# PCIe.net
KiCad netlist of a schematic drawn in Altium Designer
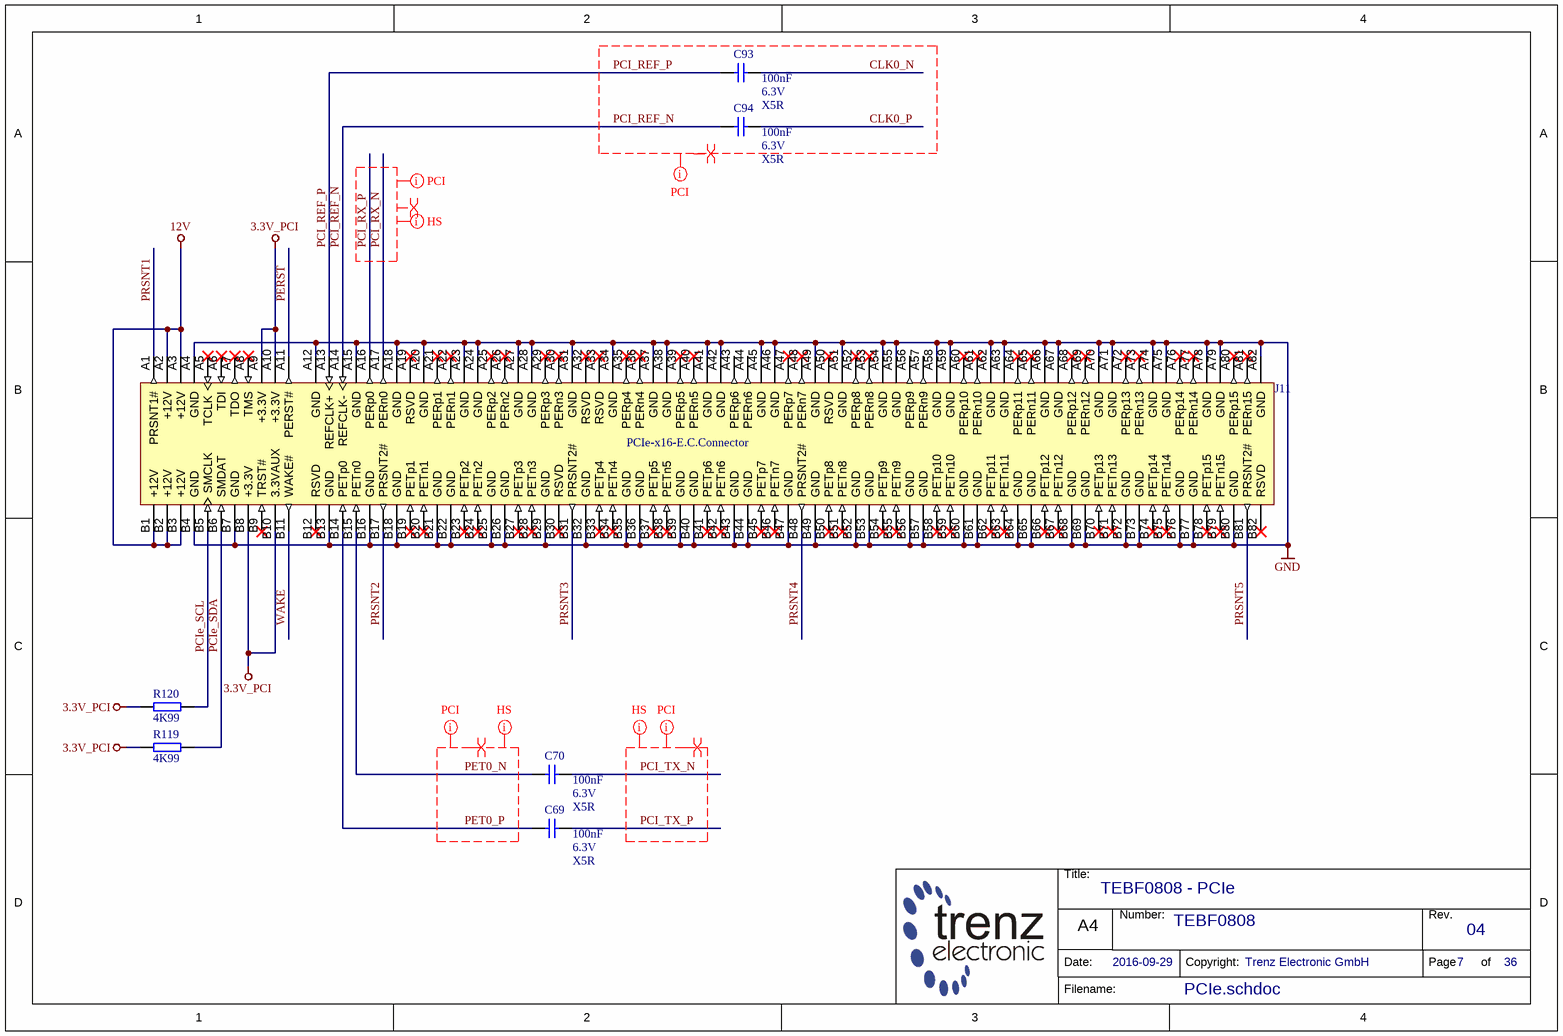
[diagram p0: PCIe.schdoc]

(export (version "E")
  (design (tool "Eeschema 10.0.6"))
  (components
    (comp (ref "C69")
      (value "100nF")
      (footprint "CAPC0603X33N")
      (description "KON 100nF 6.3V X5R SMD 10%")
      (fields
        (field (name "VOLTAGE") "6.3V")
        (field (name "TECHNOLOGY") "X5R")
        (field (name "TOLERANCE") "10%")
      )
      (libsource (lib "TE") (part "CAP-NP"))
    )
    (comp (ref "C70")
      (value "100nF")
      (footprint "CAPC0603X33N")
      (description "KON 100nF 6.3V X5R SMD 10%")
      (fields
        (field (name "VOLTAGE") "6.3V")
        (field (name "TECHNOLOGY") "X5R")
        (field (name "TOLERANCE") "10%")
      )
      (libsource (lib "TE") (part "CAP-NP"))
    )
    (comp (ref "C93")
      (value "100nF")
      (footprint "CAPC0603X33N")
      (description "KON 100nF 6.3V X5R SMD 10%")
      (fields
        (field (name "VOLTAGE") "6.3V")
        (field (name "TECHNOLOGY") "X5R")
        (field (name "TOLERANCE") "10%")
      )
      (libsource (lib "TE") (part "CAP-NP"))
    )
    (comp (ref "C94")
      (value "100nF")
      (footprint "CAPC0603X33N")
      (description "KON 100nF 6.3V X5R SMD 10%")
      (fields
        (field (name "VOLTAGE") "6.3V")
        (field (name "TECHNOLOGY") "X5R")
        (field (name "TOLERANCE") "10%")
      )
      (libsource (lib "TE") (part "CAP-NP"))
    )
    (comp (ref "J11")
      (value "PCIe-x16-E.C.Connector")
      (footprint "PCIe-x16-E.C.Connector")
      (description "PCIe-x16, 30µin, Twin Plastic, Black")
      (libsource (lib "TE") (part "PCIe-x16-E.C.Connector"))
    )
    (comp (ref "R119")
      (value "4K99")
      (footprint "RESC1005X40N")
      (description "WID SMD 4K99 1% 0,063W")
      (fields (field (name "TOLERANCE") "1%"))
      (libsource (lib "TE") (part "RES"))
    )
    (comp (ref "R120")
      (value "4K99")
      (footprint "RESC1005X40N")
      (description "WID SMD 4K99 1% 0,063W")
      (fields (field (name "TOLERANCE") "1%"))
      (libsource (lib "TE") (part "RES"))
    )
  )
  (nets
    (net (code "1") (name "/CLK0_N") (class "Default")
      (node (ref "C93") (pin "2") (pinfunction "2_2") (pintype "passive"))
    )
    (net (code "2") (name "/CLK0_P") (class "Default")
      (node (ref "C94") (pin "2") (pinfunction "2_2") (pintype "passive"))
    )
    (net (code "3") (name "/PCI_REF_N") (class "Default")
      (node (ref "C94") (pin "1") (pinfunction "1_1") (pintype "passive"))
      (node (ref "J11") (pin "A14") (pinfunction "REFCLK-_A14") (pintype "input"))
    )
    (net (code "4") (name "/PCI_REF_P") (class "Default")
      (node (ref "C93") (pin "1") (pinfunction "1_1") (pintype "passive"))
      (node (ref "J11") (pin "A13") (pinfunction "REFCLK+_A13") (pintype "input"))
    )
    (net (code "5") (name "/PCI_RX_N") (class "Default")
      (node (ref "J11") (pin "A17") (pinfunction "PERn0_A17") (pintype "output"))
    )
    (net (code "6") (name "/PCI_RX_P") (class "Default")
      (node (ref "J11") (pin "A16") (pinfunction "PERp0_A16") (pintype "output"))
    )
    (net (code "7") (name "/PCI_TX_N") (class "Default")
      (node (ref "C70") (pin "2") (pinfunction "2_2") (pintype "passive"))
    )
    (net (code "8") (name "/PCI_TX_P") (class "Default")
      (node (ref "C69") (pin "2") (pinfunction "2_2") (pintype "passive"))
    )
    (net (code "9") (name "/PCIe_SCL") (class "Default")
      (node (ref "J11") (pin "B5") (pinfunction "SMCLK_B5") (pintype "input"))
      (node (ref "R120") (pin "2") (pinfunction "2_2") (pintype "passive"))
    )
    (net (code "10") (name "/PCIe_SDA") (class "Default")
      (node (ref "J11") (pin "B6") (pinfunction "SMDAT_B6") (pintype "input"))
      (node (ref "R119") (pin "2") (pinfunction "2_2") (pintype "passive"))
    )
    (net (code "11") (name "/PERST") (class "Default")
      (node (ref "J11") (pin "A11") (pinfunction "PERST#_A11") (pintype "output"))
    )
    (net (code "12") (name "/PET0_N") (class "Default")
      (node (ref "C70") (pin "1") (pinfunction "1_1") (pintype "passive"))
      (node (ref "J11") (pin "B15") (pinfunction "PETn0_B15") (pintype "input"))
    )
    (net (code "13") (name "/PET0_P") (class "Default")
      (node (ref "C69") (pin "1") (pinfunction "1_1") (pintype "passive"))
      (node (ref "J11") (pin "B14") (pinfunction "PETp0_B14") (pintype "input"))
    )
    (net (code "14") (name "/PRSNT1") (class "Default")
      (node (ref "J11") (pin "A1") (pinfunction "PRSNT1#_A1") (pintype "output"))
    )
    (net (code "15") (name "/PRSNT2") (class "Default")
      (node (ref "J11") (pin "B17") (pinfunction "PRSNT2#_B17") (pintype "output"))
    )
    (net (code "16") (name "/PRSNT3") (class "Default")
      (node (ref "J11") (pin "B31") (pinfunction "PRSNT2#_B31") (pintype "output"))
    )
    (net (code "17") (name "/PRSNT4") (class "Default")
      (node (ref "J11") (pin "B48") (pinfunction "PRSNT2#_B48") (pintype "output"))
    )
    (net (code "18") (name "/PRSNT5") (class "Default")
      (node (ref "J11") (pin "B81") (pinfunction "PRSNT2#_B81") (pintype "output"))
    )
    (net (code "19") (name "/WAKE") (class "Default")
      (node (ref "J11") (pin "B11") (pinfunction "WAKE#_B11") (pintype "output"))
    )
    (net (code "20") (name "3.3V_PCI") (class "Default")
      (node (ref "J11") (pin "A10") (pinfunction "+3.3V_A10") (pintype "power_in"))
      (node (ref "J11") (pin "A9") (pinfunction "+3.3V_A9") (pintype "power_in"))
      (node (ref "J11") (pin "B10") (pinfunction "3.3VAUX_B10") (pintype "power_in"))
      (node (ref "J11") (pin "B8") (pinfunction "+3.3V_B8") (pintype "power_in"))
      (node (ref "R119") (pin "1") (pinfunction "1_1") (pintype "passive"))
      (node (ref "R120") (pin "1") (pinfunction "1_1") (pintype "passive"))
    )
    (net (code "21") (name "12V") (class "Default")
      (node (ref "J11") (pin "A2") (pinfunction "+12V_A2") (pintype "power_in"))
      (node (ref "J11") (pin "A3") (pinfunction "+12V_A3") (pintype "power_in"))
      (node (ref "J11") (pin "B1") (pinfunction "+12V_B1") (pintype "power_in"))
      (node (ref "J11") (pin "B2") (pinfunction "+12V_B2") (pintype "power_in"))
      (node (ref "J11") (pin "B3") (pinfunction "+12V_B3") (pintype "power_in"))
    )
    (net (code "22") (name "GND") (class "Default")
      (node (ref "J11") (pin "A12") (pinfunction "GND_A12") (pintype "power_in"))
      (node (ref "J11") (pin "A15") (pinfunction "GND_A15") (pintype "power_in"))
      (node (ref "J11") (pin "A18") (pinfunction "GND_A18") (pintype "power_in"))
      (node (ref "J11") (pin "A20") (pinfunction "GND_A20") (pintype "power_in"))
      (node (ref "J11") (pin "A23") (pinfunction "GND_A23") (pintype "power_in"))
      (node (ref "J11") (pin "A24") (pinfunction "GND_A24") (pintype "power_in"))
      (node (ref "J11") (pin "A27") (pinfunction "GND_A27") (pintype "power_in"))
      (node (ref "J11") (pin "A28") (pinfunction "GND_A28") (pintype "power_in"))
      (node (ref "J11") (pin "A31") (pinfunction "GND_A31") (pintype "power_in"))
      (node (ref "J11") (pin "A34") (pinfunction "GND_A34") (pintype "power_in"))
      (node (ref "J11") (pin "A37") (pinfunction "GND_A37") (pintype "power_in"))
      (node (ref "J11") (pin "A38") (pinfunction "GND_A38") (pintype "power_in"))
      (node (ref "J11") (pin "A4") (pinfunction "GND_A4") (pintype "power_in"))
      (node (ref "J11") (pin "A41") (pinfunction "GND_A41") (pintype "power_in"))
      (node (ref "J11") (pin "A42") (pinfunction "GND_A42") (pintype "power_in"))
      (node (ref "J11") (pin "A45") (pinfunction "GND_A45") (pintype "power_in"))
      (node (ref "J11") (pin "A46") (pinfunction "GND_A46") (pintype "power_in"))
      (node (ref "J11") (pin "A49") (pinfunction "GND_A49") (pintype "power_in"))
      (node (ref "J11") (pin "A51") (pinfunction "GND_A51") (pintype "power_in"))
      (node (ref "J11") (pin "A54") (pinfunction "GND_A54") (pintype "power_in"))
      (node (ref "J11") (pin "A55") (pinfunction "GND_A55") (pintype "power_in"))
      (node (ref "J11") (pin "A58") (pinfunction "GND_A58") (pintype "power_in"))
      (node (ref "J11") (pin "A59") (pinfunction "GND_A59") (pintype "power_in"))
      (node (ref "J11") (pin "A62") (pinfunction "GND_A62") (pintype "power_in"))
      (node (ref "J11") (pin "A63") (pinfunction "GND_A63") (pintype "power_in"))
      (node (ref "J11") (pin "A66") (pinfunction "GND_A66") (pintype "power_in"))
      (node (ref "J11") (pin "A67") (pinfunction "GND_A67") (pintype "power_in"))
      (node (ref "J11") (pin "A70") (pinfunction "GND_A70") (pintype "power_in"))
      (node (ref "J11") (pin "A71") (pinfunction "GND_A71") (pintype "power_in"))
      (node (ref "J11") (pin "A74") (pinfunction "GND_A74") (pintype "power_in"))
      (node (ref "J11") (pin "A75") (pinfunction "GND_A75") (pintype "power_in"))
      (node (ref "J11") (pin "A78") (pinfunction "GND_A78") (pintype "power_in"))
      (node (ref "J11") (pin "A79") (pinfunction "GND_A79") (pintype "power_in"))
      (node (ref "J11") (pin "A82") (pinfunction "GND_A82") (pintype "power_in"))
      (node (ref "J11") (pin "B13") (pinfunction "GND_B13") (pintype "power_in"))
      (node (ref "J11") (pin "B16") (pinfunction "GND_B16") (pintype "power_in"))
      (node (ref "J11") (pin "B18") (pinfunction "GND_B18") (pintype "power_in"))
      (node (ref "J11") (pin "B21") (pinfunction "GND_B21") (pintype "power_in"))
      (node (ref "J11") (pin "B22") (pinfunction "GND_B22") (pintype "power_in"))
      (node (ref "J11") (pin "B25") (pinfunction "GND_B25") (pintype "power_in"))
      (node (ref "J11") (pin "B26") (pinfunction "GND_B26") (pintype "power_in"))
      (node (ref "J11") (pin "B29") (pinfunction "GND_B29") (pintype "power_in"))
      (node (ref "J11") (pin "B32") (pinfunction "GND_B32") (pintype "power_in"))
      (node (ref "J11") (pin "B35") (pinfunction "GND_B35") (pintype "power_in"))
      (node (ref "J11") (pin "B36") (pinfunction "GND_B36") (pintype "power_in"))
      (node (ref "J11") (pin "B39") (pinfunction "GND_B39") (pintype "power_in"))
      (node (ref "J11") (pin "B4") (pinfunction "GND_B4") (pintype "power_in"))
      (node (ref "J11") (pin "B40") (pinfunction "GND_B40") (pintype "power_in"))
      (node (ref "J11") (pin "B43") (pinfunction "GND_B43") (pintype "power_in"))
      (node (ref "J11") (pin "B44") (pinfunction "GND_B44") (pintype "power_in"))
      (node (ref "J11") (pin "B47") (pinfunction "GND_B47") (pintype "power_in"))
      (node (ref "J11") (pin "B49") (pinfunction "GND_B49") (pintype "power_in"))
      (node (ref "J11") (pin "B52") (pinfunction "GND_B52") (pintype "power_in"))
      (node (ref "J11") (pin "B53") (pinfunction "GND_B53") (pintype "power_in"))
      (node (ref "J11") (pin "B56") (pinfunction "GND_B56") (pintype "power_in"))
      (node (ref "J11") (pin "B57") (pinfunction "GND_B57") (pintype "power_in"))
      (node (ref "J11") (pin "B60") (pinfunction "GND_B60") (pintype "power_in"))
      (node (ref "J11") (pin "B61") (pinfunction "GND_B61") (pintype "power_in"))
      (node (ref "J11") (pin "B64") (pinfunction "GND_B64") (pintype "power_in"))
      (node (ref "J11") (pin "B65") (pinfunction "GND_B65") (pintype "power_in"))
      (node (ref "J11") (pin "B68") (pinfunction "GND_B68") (pintype "power_in"))
      (node (ref "J11") (pin "B69") (pinfunction "GND_B69") (pintype "power_in"))
      (node (ref "J11") (pin "B7") (pinfunction "GND_B7") (pintype "power_in"))
      (node (ref "J11") (pin "B72") (pinfunction "GND_B72") (pintype "power_in"))
      (node (ref "J11") (pin "B73") (pinfunction "GND_B73") (pintype "power_in"))
      (node (ref "J11") (pin "B76") (pinfunction "GND_B76") (pintype "power_in"))
      (node (ref "J11") (pin "B77") (pinfunction "GND_B77") (pintype "power_in"))
      (node (ref "J11") (pin "B80") (pinfunction "GND_B80") (pintype "power_in"))
    )
    (net (code "23") (name "unconnected-(J11-PERn1-PadA22)") (class "Default")
      (node (ref "J11") (pin "A22") (pinfunction "PERn1_A22") (pintype "output+no_connect"))
    )
    (net (code "24") (name "unconnected-(J11-PERn2-PadA26)") (class "Default")
      (node (ref "J11") (pin "A26") (pinfunction "PERn2_A26") (pintype "output+no_connect"))
    )
    (net (code "25") (name "unconnected-(J11-PERn3-PadA30)") (class "Default")
      (node (ref "J11") (pin "A30") (pinfunction "PERn3_A30") (pintype "output+no_connect"))
    )
    (net (code "26") (name "unconnected-(J11-PERn4-PadA36)") (class "Default")
      (node (ref "J11") (pin "A36") (pinfunction "PERn4_A36") (pintype "output+no_connect"))
    )
    (net (code "27") (name "unconnected-(J11-PERn5-PadA40)") (class "Default")
      (node (ref "J11") (pin "A40") (pinfunction "PERn5_A40") (pintype "output+no_connect"))
    )
    (net (code "28") (name "unconnected-(J11-PERn6-PadA44)") (class "Default")
      (node (ref "J11") (pin "A44") (pinfunction "PERn6_A44") (pintype "output"))
    )
    (net (code "29") (name "unconnected-(J11-PERn7-PadA48)") (class "Default")
      (node (ref "J11") (pin "A48") (pinfunction "PERn7_A48") (pintype "output+no_connect"))
    )
    (net (code "30") (name "unconnected-(J11-PERn8-PadA53)") (class "Default")
      (node (ref "J11") (pin "A53") (pinfunction "PERn8_A53") (pintype "output+no_connect"))
    )
    (net (code "31") (name "unconnected-(J11-PERn9-PadA57)") (class "Default")
      (node (ref "J11") (pin "A57") (pinfunction "PERn9_A57") (pintype "output"))
    )
    (net (code "32") (name "unconnected-(J11-PERn10-PadA61)") (class "Default")
      (node (ref "J11") (pin "A61") (pinfunction "PERn10_A61") (pintype "output+no_connect"))
    )
    (net (code "33") (name "unconnected-(J11-PERn11-PadA65)") (class "Default")
      (node (ref "J11") (pin "A65") (pinfunction "PERn11_A65") (pintype "output+no_connect"))
    )
    (net (code "34") (name "unconnected-(J11-PERn12-PadA69)") (class "Default")
      (node (ref "J11") (pin "A69") (pinfunction "PERn12_A69") (pintype "output+no_connect"))
    )
    (net (code "35") (name "unconnected-(J11-PERn13-PadA73)") (class "Default")
      (node (ref "J11") (pin "A73") (pinfunction "PERn13_A73") (pintype "output+no_connect"))
    )
    (net (code "36") (name "unconnected-(J11-PERn14-PadA77)") (class "Default")
      (node (ref "J11") (pin "A77") (pinfunction "PERn14_A77") (pintype "output+no_connect"))
    )
    (net (code "37") (name "unconnected-(J11-PERn15-PadA81)") (class "Default")
      (node (ref "J11") (pin "A81") (pinfunction "PERn15_A81") (pintype "output+no_connect"))
    )
    (net (code "38") (name "unconnected-(J11-PERp1-PadA21)") (class "Default")
      (node (ref "J11") (pin "A21") (pinfunction "PERp1_A21") (pintype "output+no_connect"))
    )
    (net (code "39") (name "unconnected-(J11-PERp2-PadA25)") (class "Default")
      (node (ref "J11") (pin "A25") (pinfunction "PERp2_A25") (pintype "output+no_connect"))
    )
    (net (code "40") (name "unconnected-(J11-PERp3-PadA29)") (class "Default")
      (node (ref "J11") (pin "A29") (pinfunction "PERp3_A29") (pintype "output+no_connect"))
    )
    (net (code "41") (name "unconnected-(J11-PERp4-PadA35)") (class "Default")
      (node (ref "J11") (pin "A35") (pinfunction "PERp4_A35") (pintype "output+no_connect"))
    )
    (net (code "42") (name "unconnected-(J11-PERp5-PadA39)") (class "Default")
      (node (ref "J11") (pin "A39") (pinfunction "PERp5_A39") (pintype "output+no_connect"))
    )
    (net (code "43") (name "unconnected-(J11-PERp6-PadA43)") (class "Default")
      (node (ref "J11") (pin "A43") (pinfunction "PERp6_A43") (pintype "output"))
    )
    (net (code "44") (name "unconnected-(J11-PERp7-PadA47)") (class "Default")
      (node (ref "J11") (pin "A47") (pinfunction "PERp7_A47") (pintype "output+no_connect"))
    )
    (net (code "45") (name "unconnected-(J11-PERp8-PadA52)") (class "Default")
      (node (ref "J11") (pin "A52") (pinfunction "PERp8_A52") (pintype "output+no_connect"))
    )
    (net (code "46") (name "unconnected-(J11-PERp9-PadA56)") (class "Default")
      (node (ref "J11") (pin "A56") (pinfunction "PERp9_A56") (pintype "output"))
    )
    (net (code "47") (name "unconnected-(J11-PERp10-PadA60)") (class "Default")
      (node (ref "J11") (pin "A60") (pinfunction "PERp10_A60") (pintype "output+no_connect"))
    )
    (net (code "48") (name "unconnected-(J11-PERp11-PadA64)") (class "Default")
      (node (ref "J11") (pin "A64") (pinfunction "PERp11_A64") (pintype "output+no_connect"))
    )
    (net (code "49") (name "unconnected-(J11-PERp12-PadA68)") (class "Default")
      (node (ref "J11") (pin "A68") (pinfunction "PERp12_A68") (pintype "output+no_connect"))
    )
    (net (code "50") (name "unconnected-(J11-PERp13-PadA72)") (class "Default")
      (node (ref "J11") (pin "A72") (pinfunction "PERp13_A72") (pintype "output+no_connect"))
    )
    (net (code "51") (name "unconnected-(J11-PERp14-PadA76)") (class "Default")
      (node (ref "J11") (pin "A76") (pinfunction "PERp14_A76") (pintype "output+no_connect"))
    )
    (net (code "52") (name "unconnected-(J11-PERp15-PadA80)") (class "Default")
      (node (ref "J11") (pin "A80") (pinfunction "PERp15_A80") (pintype "output+no_connect"))
    )
    (net (code "53") (name "unconnected-(J11-PETn1-PadB20)") (class "Default")
      (node (ref "J11") (pin "B20") (pinfunction "PETn1_B20") (pintype "input+no_connect"))
    )
    (net (code "54") (name "unconnected-(J11-PETn2-PadB24)") (class "Default")
      (node (ref "J11") (pin "B24") (pinfunction "PETn2_B24") (pintype "input+no_connect"))
    )
    (net (code "55") (name "unconnected-(J11-PETn3-PadB28)") (class "Default")
      (node (ref "J11") (pin "B28") (pinfunction "PETn3_B28") (pintype "input+no_connect"))
    )
    (net (code "56") (name "unconnected-(J11-PETn4-PadB34)") (class "Default")
      (node (ref "J11") (pin "B34") (pinfunction "PETn4_B34") (pintype "input+no_connect"))
    )
    (net (code "57") (name "unconnected-(J11-PETn5-PadB38)") (class "Default")
      (node (ref "J11") (pin "B38") (pinfunction "PETn5_B38") (pintype "input+no_connect"))
    )
    (net (code "58") (name "unconnected-(J11-PETn6-PadB42)") (class "Default")
      (node (ref "J11") (pin "B42") (pinfunction "PETn6_B42") (pintype "input+no_connect"))
    )
    (net (code "59") (name "unconnected-(J11-PETn7-PadB46)") (class "Default")
      (node (ref "J11") (pin "B46") (pinfunction "PETn7_B46") (pintype "input+no_connect"))
    )
    (net (code "60") (name "unconnected-(J11-PETn8-PadB51)") (class "Default")
      (node (ref "J11") (pin "B51") (pinfunction "PETn8_B51") (pintype "input+no_connect"))
    )
    (net (code "61") (name "unconnected-(J11-PETn9-PadB55)") (class "Default")
      (node (ref "J11") (pin "B55") (pinfunction "PETn9_B55") (pintype "input+no_connect"))
    )
    (net (code "62") (name "unconnected-(J11-PETn10-PadB59)") (class "Default")
      (node (ref "J11") (pin "B59") (pinfunction "PETn10_B59") (pintype "input+no_connect"))
    )
    (net (code "63") (name "unconnected-(J11-PETn11-PadB63)") (class "Default")
      (node (ref "J11") (pin "B63") (pinfunction "PETn11_B63") (pintype "input+no_connect"))
    )
    (net (code "64") (name "unconnected-(J11-PETn12-PadB67)") (class "Default")
      (node (ref "J11") (pin "B67") (pinfunction "PETn12_B67") (pintype "input+no_connect"))
    )
    (net (code "65") (name "unconnected-(J11-PETn13-PadB71)") (class "Default")
      (node (ref "J11") (pin "B71") (pinfunction "PETn13_B71") (pintype "input+no_connect"))
    )
    (net (code "66") (name "unconnected-(J11-PETn14-PadB75)") (class "Default")
      (node (ref "J11") (pin "B75") (pinfunction "PETn14_B75") (pintype "input+no_connect"))
    )
    (net (code "67") (name "unconnected-(J11-PETn15-PadB79)") (class "Default")
      (node (ref "J11") (pin "B79") (pinfunction "PETn15_B79") (pintype "input+no_connect"))
    )
    (net (code "68") (name "unconnected-(J11-PETp1-PadB19)") (class "Default")
      (node (ref "J11") (pin "B19") (pinfunction "PETp1_B19") (pintype "input+no_connect"))
    )
    (net (code "69") (name "unconnected-(J11-PETp2-PadB23)") (class "Default")
      (node (ref "J11") (pin "B23") (pinfunction "PETp2_B23") (pintype "input+no_connect"))
    )
    (net (code "70") (name "unconnected-(J11-PETp3-PadB27)") (class "Default")
      (node (ref "J11") (pin "B27") (pinfunction "PETp3_B27") (pintype "input+no_connect"))
    )
    (net (code "71") (name "unconnected-(J11-PETp4-PadB33)") (class "Default")
      (node (ref "J11") (pin "B33") (pinfunction "PETp4_B33") (pintype "input+no_connect"))
    )
    (net (code "72") (name "unconnected-(J11-PETp5-PadB37)") (class "Default")
      (node (ref "J11") (pin "B37") (pinfunction "PETp5_B37") (pintype "input+no_connect"))
    )
    (net (code "73") (name "unconnected-(J11-PETp6-PadB41)") (class "Default")
      (node (ref "J11") (pin "B41") (pinfunction "PETp6_B41") (pintype "input+no_connect"))
    )
    (net (code "74") (name "unconnected-(J11-PETp7-PadB45)") (class "Default")
      (node (ref "J11") (pin "B45") (pinfunction "PETp7_B45") (pintype "input+no_connect"))
    )
    (net (code "75") (name "unconnected-(J11-PETp8-PadB50)") (class "Default")
      (node (ref "J11") (pin "B50") (pinfunction "PETp8_B50") (pintype "input+no_connect"))
    )
    (net (code "76") (name "unconnected-(J11-PETp9-PadB54)") (class "Default")
      (node (ref "J11") (pin "B54") (pinfunction "PETp9_B54") (pintype "input+no_connect"))
    )
    (net (code "77") (name "unconnected-(J11-PETp10-PadB58)") (class "Default")
      (node (ref "J11") (pin "B58") (pinfunction "PETp10_B58") (pintype "input+no_connect"))
    )
    (net (code "78") (name "unconnected-(J11-PETp11-PadB62)") (class "Default")
      (node (ref "J11") (pin "B62") (pinfunction "PETp11_B62") (pintype "input+no_connect"))
    )
    (net (code "79") (name "unconnected-(J11-PETp12-PadB66)") (class "Default")
      (node (ref "J11") (pin "B66") (pinfunction "PETp12_B66") (pintype "input+no_connect"))
    )
    (net (code "80") (name "unconnected-(J11-PETp13-PadB70)") (class "Default")
      (node (ref "J11") (pin "B70") (pinfunction "PETp13_B70") (pintype "input+no_connect"))
    )
    (net (code "81") (name "unconnected-(J11-PETp14-PadB74)") (class "Default")
      (node (ref "J11") (pin "B74") (pinfunction "PETp14_B74") (pintype "input+no_connect"))
    )
    (net (code "82") (name "unconnected-(J11-PETp15-PadB78)") (class "Default")
      (node (ref "J11") (pin "B78") (pinfunction "PETp15_B78") (pintype "input+no_connect"))
    )
    (net (code "83") (name "unconnected-(J11-RSVD-PadA19)") (class "Default")
      (node (ref "J11") (pin "A19") (pinfunction "RSVD_A19") (pintype "passive+no_connect"))
    )
    (net (code "84") (name "unconnected-(J11-RSVD-PadA32)") (class "Default")
      (node (ref "J11") (pin "A32") (pinfunction "RSVD_A32") (pintype "passive+no_connect"))
    )
    (net (code "85") (name "unconnected-(J11-RSVD-PadA33)") (class "Default")
      (node (ref "J11") (pin "A33") (pinfunction "RSVD_A33") (pintype "passive+no_connect"))
    )
    (net (code "86") (name "unconnected-(J11-RSVD-PadA50)") (class "Default")
      (node (ref "J11") (pin "A50") (pinfunction "RSVD_A50") (pintype "passive+no_connect"))
    )
    (net (code "87") (name "unconnected-(J11-RSVD-PadB12)") (class "Default")
      (node (ref "J11") (pin "B12") (pinfunction "RSVD_B12") (pintype "passive+no_connect"))
    )
    (net (code "88") (name "unconnected-(J11-RSVD-PadB30)") (class "Default")
      (node (ref "J11") (pin "B30") (pinfunction "RSVD_B30") (pintype "passive+no_connect"))
    )
    (net (code "89") (name "unconnected-(J11-RSVD-PadB82)") (class "Default")
      (node (ref "J11") (pin "B82") (pinfunction "RSVD_B82") (pintype "passive+no_connect"))
    )
    (net (code "90") (name "unconnected-(J11-TCLK-PadA5)") (class "Default")
      (node (ref "J11") (pin "A5") (pinfunction "TCLK_A5") (pintype "input+no_connect"))
    )
    (net (code "91") (name "unconnected-(J11-TDI-PadA6)") (class "Default")
      (node (ref "J11") (pin "A6") (pinfunction "TDI_A6") (pintype "input+no_connect"))
    )
    (net (code "92") (name "unconnected-(J11-TDO-PadA7)") (class "Default")
      (node (ref "J11") (pin "A7") (pinfunction "TDO_A7") (pintype "output+no_connect"))
    )
    (net (code "93") (name "unconnected-(J11-TMS-PadA8)") (class "Default")
      (node (ref "J11") (pin "A8") (pinfunction "TMS_A8") (pintype "input+no_connect"))
    )
    (net (code "94") (name "unconnected-(J11-TRST#-PadB9)") (class "Default")
      (node (ref "J11") (pin "B9") (pinfunction "TRST#_B9") (pintype "input+no_connect"))
    )
  )
)
